# RPiDuino_revA.net
KiCad netlist of a schematic drawn in EAGLE
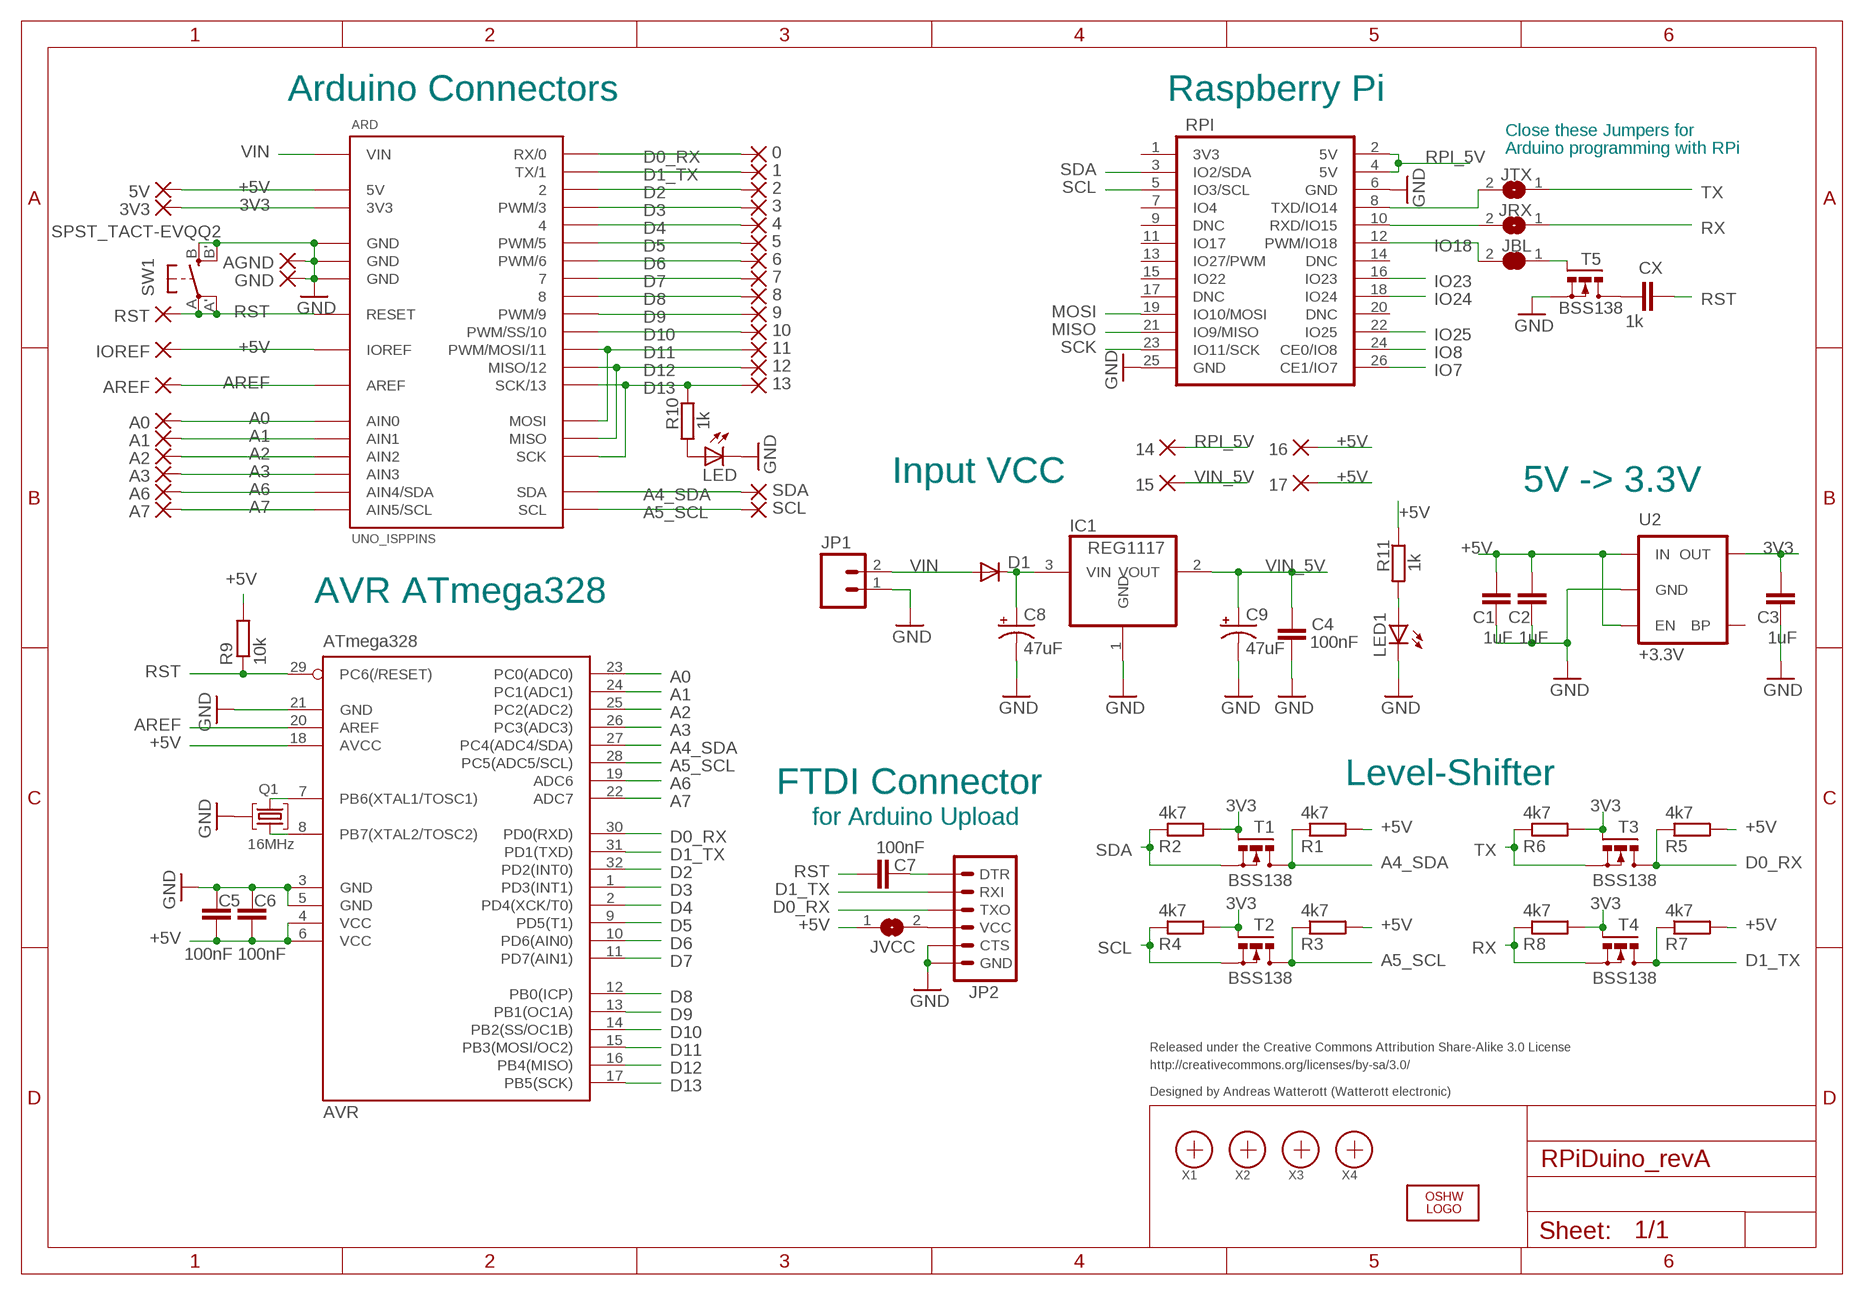
[diagram p0: schematic, sheet 1]

(export (version "E")
  (design (tool "Eeschema 10.0.6"))
  (components
    (comp (ref "0")
      (value "WIREPAD1,6/0,9")
      (footprint "eagle-import:1,6_0,9")
      (libsource (lib "eagle-import") (part "WIREPAD1,6/0,9"))
    )
    (comp (ref "1")
      (value "WIREPAD1,6/0,9")
      (footprint "eagle-import:1,6_0,9")
      (libsource (lib "eagle-import") (part "WIREPAD1,6/0,9"))
    )
    (comp (ref "2")
      (value "WIREPAD1,6/0,9")
      (footprint "eagle-import:1,6_0,9")
      (libsource (lib "eagle-import") (part "WIREPAD1,6/0,9"))
    )
    (comp (ref "3")
      (value "WIREPAD1,6/0,9")
      (footprint "eagle-import:1,6_0,9")
      (libsource (lib "eagle-import") (part "WIREPAD1,6/0,9"))
    )
    (comp (ref "3V3")
      (value "WIREPAD1,6/0,9")
      (footprint "eagle-import:1,6_0,9")
      (libsource (lib "eagle-import") (part "WIREPAD1,6/0,9"))
    )
    (comp (ref "4")
      (value "WIREPAD1,6/0,9")
      (footprint "eagle-import:1,6_0,9")
      (libsource (lib "eagle-import") (part "WIREPAD1,6/0,9"))
    )
    (comp (ref "5")
      (value "WIREPAD1,6/0,9")
      (footprint "eagle-import:1,6_0,9")
      (libsource (lib "eagle-import") (part "WIREPAD1,6/0,9"))
    )
    (comp (ref "5V")
      (value "WIREPAD1,6/0,9")
      (footprint "eagle-import:1,6_0,9")
      (libsource (lib "eagle-import") (part "WIREPAD1,6/0,9"))
    )
    (comp (ref "6")
      (value "WIREPAD1,6/0,9")
      (footprint "eagle-import:1,6_0,9")
      (libsource (lib "eagle-import") (part "WIREPAD1,6/0,9"))
    )
    (comp (ref "7")
      (value "WIREPAD1,6/0,9")
      (footprint "eagle-import:1,6_0,9")
      (libsource (lib "eagle-import") (part "WIREPAD1,6/0,9"))
    )
    (comp (ref "8")
      (value "WIREPAD1,6/0,9")
      (footprint "eagle-import:1,6_0,9")
      (libsource (lib "eagle-import") (part "WIREPAD1,6/0,9"))
    )
    (comp (ref "9")
      (value "WIREPAD1,6/0,9")
      (footprint "eagle-import:1,6_0,9")
      (libsource (lib "eagle-import") (part "WIREPAD1,6/0,9"))
    )
    (comp (ref "10")
      (value "WIREPAD1,6/0,9")
      (footprint "eagle-import:1,6_0,9")
      (libsource (lib "eagle-import") (part "WIREPAD1,6/0,9"))
    )
    (comp (ref "11")
      (value "WIREPAD1,6/0,9")
      (footprint "eagle-import:1,6_0,9")
      (libsource (lib "eagle-import") (part "WIREPAD1,6/0,9"))
    )
    (comp (ref "12")
      (value "WIREPAD1,6/0,9")
      (footprint "eagle-import:1,6_0,9")
      (libsource (lib "eagle-import") (part "WIREPAD1,6/0,9"))
    )
    (comp (ref "13")
      (value "WIREPAD1,6/0,9")
      (footprint "eagle-import:1,6_0,9")
      (libsource (lib "eagle-import") (part "WIREPAD1,6/0,9"))
    )
    (comp (ref "14")
      (value "WIREPAD1,6/0,9")
      (footprint "eagle-import:1,6_0,9")
      (libsource (lib "eagle-import") (part "WIREPAD1,6/0,9"))
    )
    (comp (ref "15")
      (value "WIREPAD1,6/0,9")
      (footprint "eagle-import:1,6_0,9")
      (libsource (lib "eagle-import") (part "WIREPAD1,6/0,9"))
    )
    (comp (ref "16")
      (value "WIREPAD1,6/0,9")
      (footprint "eagle-import:1,6_0,9")
      (libsource (lib "eagle-import") (part "WIREPAD1,6/0,9"))
    )
    (comp (ref "17")
      (value "WIREPAD1,6/0,9")
      (footprint "eagle-import:1,6_0,9")
      (libsource (lib "eagle-import") (part "WIREPAD1,6/0,9"))
    )
    (comp (ref "A0")
      (value "WIREPAD1,6/0,9")
      (footprint "eagle-import:1,6_0,9")
      (libsource (lib "eagle-import") (part "WIREPAD1,6/0,9"))
    )
    (comp (ref "A1")
      (value "WIREPAD1,6/0,9")
      (footprint "eagle-import:1,6_0,9")
      (libsource (lib "eagle-import") (part "WIREPAD1,6/0,9"))
    )
    (comp (ref "A2")
      (value "WIREPAD1,6/0,9")
      (footprint "eagle-import:1,6_0,9")
      (libsource (lib "eagle-import") (part "WIREPAD1,6/0,9"))
    )
    (comp (ref "A3")
      (value "WIREPAD1,6/0,9")
      (footprint "eagle-import:1,6_0,9")
      (libsource (lib "eagle-import") (part "WIREPAD1,6/0,9"))
    )
    (comp (ref "A6")
      (value "WIREPAD1,6/0,9")
      (footprint "eagle-import:1,6_0,9")
      (libsource (lib "eagle-import") (part "WIREPAD1,6/0,9"))
    )
    (comp (ref "A7")
      (value "WIREPAD1,6/0,9")
      (footprint "eagle-import:1,6_0,9")
      (libsource (lib "eagle-import") (part "WIREPAD1,6/0,9"))
    )
    (comp (ref "AGND")
      (value "WIREPAD1,6/0,9")
      (footprint "eagle-import:1,6_0,9")
      (libsource (lib "eagle-import") (part "WIREPAD1,6/0,9"))
    )
    (comp (ref "ARD")
      (value "UNO_ISPPINS")
      (footprint "eagle-import:UNO_ISP3")
      (libsource (lib "eagle-import") (part "UNO_ISPPINS"))
    )
    (comp (ref "AREF")
      (value "WIREPAD1,6/0,9")
      (footprint "eagle-import:1,6_0,9")
      (libsource (lib "eagle-import") (part "WIREPAD1,6/0,9"))
    )
    (comp (ref "AVR")
      (value "ATmega328")
      (footprint "eagle-import:TQFP32-08")
      (fields (field (name "MPN") "ATMEGA8-16AU"))
      (libsource (lib "eagle-import") (part "MEGA8-AI"))
    )
    (comp (ref "C1")
      (value "1uF")
      (footprint "eagle-import:C0603")
      (libsource (lib "eagle-import") (part "C-EUC0603"))
    )
    (comp (ref "C2")
      (value "1uF")
      (footprint "eagle-import:C0603")
      (libsource (lib "eagle-import") (part "C-EUC0603"))
    )
    (comp (ref "C3")
      (value "1uF")
      (footprint "eagle-import:C0603")
      (libsource (lib "eagle-import") (part "C-EUC0603"))
    )
    (comp (ref "C4")
      (value "100nF")
      (footprint "eagle-import:C0603")
      (libsource (lib "eagle-import") (part "C-EUC0603"))
    )
    (comp (ref "C5")
      (value "100nF")
      (footprint "eagle-import:C0603")
      (libsource (lib "eagle-import") (part "C-EUC0603"))
    )
    (comp (ref "C6")
      (value "100nF")
      (footprint "eagle-import:C0603")
      (libsource (lib "eagle-import") (part "C-EUC0603"))
    )
    (comp (ref "C7")
      (value "100nF")
      (footprint "eagle-import:C0603")
      (libsource (lib "eagle-import") (part "C-EUC0603"))
    )
    (comp (ref "C8")
      (value "47uF")
      (footprint "eagle-import:PANASONIC_D")
      (libsource (lib "eagle-import") (part "CAP_POLD"))
    )
    (comp (ref "C9")
      (value "47uF")
      (footprint "eagle-import:PANASONIC_D")
      (libsource (lib "eagle-import") (part "CAP_POLD"))
    )
    (comp (ref "CX")
      (value "1k")
      (footprint "eagle-import:C0603")
      (libsource (lib "eagle-import") (part "C-EUC0603"))
    )
    (comp (ref "D1")
      (value "DIODESMA")
      (footprint "eagle-import:SMA-DIODE")
      (libsource (lib "eagle-import") (part "DIODESMA"))
    )
    (comp (ref "GND")
      (value "WIREPAD1,6/0,9")
      (footprint "eagle-import:1,6_0,9")
      (libsource (lib "eagle-import") (part "WIREPAD1,6/0,9"))
    )
    (comp (ref "IC1")
      (value "REG1117")
      (footprint "eagle-import:SOT223")
      (libsource (lib "eagle-import") (part "REG1117"))
    )
    (comp (ref "IOREF")
      (value "WIREPAD1,6/0,9")
      (footprint "eagle-import:1,6_0,9")
      (libsource (lib "eagle-import") (part "WIREPAD1,6/0,9"))
    )
    (comp (ref "JBL") (value "SJ") (footprint "eagle-import:SJ") (libsource (lib "eagle-import") (part "SJ")))
    (comp (ref "JP1")
      (value "M02PTH")
      (footprint "eagle-import:1X02")
      (libsource (lib "eagle-import") (part "M02PTH"))
    )
    (comp (ref "JP2")
      (value "ARDUINO_SERIAL_PROGRAMPTH")
      (footprint "eagle-import:1X06")
      (libsource (lib "eagle-import") (part "ARDUINO_SERIAL_PROGRAMPTH"))
    )
    (comp (ref "JRX") (value "SJ") (footprint "eagle-import:SJ") (libsource (lib "eagle-import") (part "SJ")))
    (comp (ref "JTX") (value "SJ") (footprint "eagle-import:SJ") (libsource (lib "eagle-import") (part "SJ")))
    (comp (ref "JVCC")
      (value "SJ")
      (footprint "eagle-import:SJ")
      (libsource (lib "eagle-import") (part "SJ"))
    )
    (comp (ref "LED")
      (value "LEDCHIPLED_0603")
      (footprint "eagle-import:CHIPLED_0603")
      (libsource (lib "eagle-import") (part "LEDCHIPLED_0603"))
    )
    (comp (ref "LED1")
      (value "LEDCHIPLED_0603")
      (footprint "eagle-import:CHIPLED_0603")
      (libsource (lib "eagle-import") (part "LEDCHIPLED_0603"))
    )
    (comp (ref "LOGO1")
      (value "OSHW_LOGO_6MILX0150-NT")
      (footprint "eagle-import:OSHW_6X150_NOTEXT")
      (libsource (lib "eagle-import") (part "OSHW_LOGO_6MILX0150-NT"))
    )
    (comp (ref "Q1")
      (value "16MHz")
      (footprint "eagle-import:SMD_OSC_35X15")
      (libsource (lib "eagle-import") (part "SMD_OSC2"))
    )
    (comp (ref "R1")
      (value "4k7")
      (footprint "eagle-import:R0603")
      (libsource (lib "eagle-import") (part "R-EU_R0603"))
    )
    (comp (ref "R2")
      (value "4k7")
      (footprint "eagle-import:R0603")
      (libsource (lib "eagle-import") (part "R-EU_R0603"))
    )
    (comp (ref "R3")
      (value "4k7")
      (footprint "eagle-import:R0603")
      (libsource (lib "eagle-import") (part "R-EU_R0603"))
    )
    (comp (ref "R4")
      (value "4k7")
      (footprint "eagle-import:R0603")
      (libsource (lib "eagle-import") (part "R-EU_R0603"))
    )
    (comp (ref "R5")
      (value "4k7")
      (footprint "eagle-import:R0603")
      (libsource (lib "eagle-import") (part "R-EU_R0603"))
    )
    (comp (ref "R6")
      (value "4k7")
      (footprint "eagle-import:R0603")
      (libsource (lib "eagle-import") (part "R-EU_R0603"))
    )
    (comp (ref "R7")
      (value "4k7")
      (footprint "eagle-import:R0603")
      (libsource (lib "eagle-import") (part "R-EU_R0603"))
    )
    (comp (ref "R8")
      (value "4k7")
      (footprint "eagle-import:R0603")
      (libsource (lib "eagle-import") (part "R-EU_R0603"))
    )
    (comp (ref "R9")
      (value "10k")
      (footprint "eagle-import:R0603")
      (libsource (lib "eagle-import") (part "R-EU_R0603"))
    )
    (comp (ref "R10")
      (value "1k")
      (footprint "eagle-import:R0603")
      (libsource (lib "eagle-import") (part "R-EU_R0603"))
    )
    (comp (ref "R11")
      (value "1k")
      (footprint "eagle-import:R0603")
      (libsource (lib "eagle-import") (part "R-EU_R0603"))
    )
    (comp (ref "RPI")
      (value "RPI")
      (footprint "eagle-import:RPI")
      (libsource (lib "eagle-import") (part "RPI"))
    )
    (comp (ref "RST")
      (value "WIREPAD1,6/0,9")
      (footprint "eagle-import:1,6_0,9")
      (libsource (lib "eagle-import") (part "WIREPAD1,6/0,9"))
    )
    (comp (ref "SCL")
      (value "WIREPAD1,6/0,9")
      (footprint "eagle-import:1,6_0,9")
      (libsource (lib "eagle-import") (part "WIREPAD1,6/0,9"))
    )
    (comp (ref "SDA")
      (value "WIREPAD1,6/0,9")
      (footprint "eagle-import:1,6_0,9")
      (libsource (lib "eagle-import") (part "WIREPAD1,6/0,9"))
    )
    (comp (ref "SW1")
      (value "SPST_TACT-EVQQ2")
      (footprint "eagle-import:EVQ-Q2")
      (libsource (lib "eagle-import") (part "SPST_TACT-EVQQ2"))
    )
    (comp (ref "T1")
      (value "BSS138")
      (footprint "eagle-import:MICRO3")
      (libsource (lib "eagle-import") (part "IRLML2502"))
    )
    (comp (ref "T2")
      (value "BSS138")
      (footprint "eagle-import:MICRO3")
      (libsource (lib "eagle-import") (part "IRLML2502"))
    )
    (comp (ref "T3")
      (value "BSS138")
      (footprint "eagle-import:MICRO3")
      (libsource (lib "eagle-import") (part "IRLML2502"))
    )
    (comp (ref "T4")
      (value "BSS138")
      (footprint "eagle-import:MICRO3")
      (libsource (lib "eagle-import") (part "IRLML2502"))
    )
    (comp (ref "T5")
      (value "BSS138")
      (footprint "eagle-import:MICRO3")
      (libsource (lib "eagle-import") (part "IRLML2502"))
    )
    (comp (ref "U2")
      (value "MIC52053.3V")
      (footprint "eagle-import:SOT23-5")
      (libsource (lib "eagle-import") (part "MIC52053.3V"))
    )
    (comp (ref "X1")
      (value "PASSER")
      (footprint "eagle-import:PASSER")
      (libsource (lib "eagle-import") (part "PASSER"))
    )
    (comp (ref "X2")
      (value "PASSER")
      (footprint "eagle-import:PASSER")
      (libsource (lib "eagle-import") (part "PASSER"))
    )
    (comp (ref "X3")
      (value "PASSER")
      (footprint "eagle-import:PASSER")
      (libsource (lib "eagle-import") (part "PASSER"))
    )
    (comp (ref "X4")
      (value "PASSER")
      (footprint "eagle-import:PASSER")
      (libsource (lib "eagle-import") (part "PASSER"))
    )
  )
  (nets
    (net (code "1") (name "/+5V") (class "Default")
      (node (ref "16") (pin "1") (pinfunction "P_1") (pintype "passive"))
      (node (ref "17") (pin "1") (pinfunction "P_1") (pintype "passive"))
      (node (ref "5V") (pin "1") (pinfunction "P_1") (pintype "passive"))
      (node (ref "ARD") (pin "5V") (pinfunction "5V_5V") (pintype "power_in"))
      (node (ref "ARD") (pin "IOREF") (pinfunction "IOREF_IOREF") (pintype "power_in"))
      (node (ref "AVR") (pin "18") (pinfunction "AVCC_18") (pintype "power_in"))
      (node (ref "AVR") (pin "4") (pinfunction "VCC_4") (pintype "power_in"))
      (node (ref "AVR") (pin "6") (pinfunction "VCC_6") (pintype "power_in"))
      (node (ref "C1") (pin "1") (pinfunction "1_1") (pintype "passive"))
      (node (ref "C2") (pin "1") (pinfunction "1_1") (pintype "passive"))
      (node (ref "C5") (pin "1") (pinfunction "1_1") (pintype "passive"))
      (node (ref "C6") (pin "1") (pinfunction "1_1") (pintype "passive"))
      (node (ref "IOREF") (pin "1") (pinfunction "P_1") (pintype "passive"))
      (node (ref "JVCC") (pin "1") (pinfunction "1_1") (pintype "passive"))
      (node (ref "R1") (pin "2") (pinfunction "2_2") (pintype "passive"))
      (node (ref "R11") (pin "1") (pinfunction "1_1") (pintype "passive"))
      (node (ref "R3") (pin "2") (pinfunction "2_2") (pintype "passive"))
      (node (ref "R5") (pin "2") (pinfunction "2_2") (pintype "passive"))
      (node (ref "R7") (pin "2") (pinfunction "2_2") (pintype "passive"))
      (node (ref "R9") (pin "2") (pinfunction "2_2") (pintype "passive"))
      (node (ref "U2") (pin "1") (pinfunction "IN_1") (pintype "input"))
      (node (ref "U2") (pin "3") (pinfunction "EN_3") (pintype "input"))
    )
    (net (code "2") (name "/3V3") (class "Default")
      (node (ref "3V3") (pin "1") (pinfunction "P_1") (pintype "passive"))
      (node (ref "ARD") (pin "3V3") (pinfunction "3V3_3V3") (pintype "power_in"))
      (node (ref "C3") (pin "1") (pinfunction "1_1") (pintype "passive"))
      (node (ref "R2") (pin "2") (pinfunction "2_2") (pintype "passive"))
      (node (ref "R4") (pin "2") (pinfunction "2_2") (pintype "passive"))
      (node (ref "R6") (pin "2") (pinfunction "2_2") (pintype "passive"))
      (node (ref "R8") (pin "2") (pinfunction "2_2") (pintype "passive"))
      (node (ref "T1") (pin "1") (pinfunction "G_1") (pintype "passive"))
      (node (ref "T2") (pin "1") (pinfunction "G_1") (pintype "passive"))
      (node (ref "T3") (pin "1") (pinfunction "G_1") (pintype "passive"))
      (node (ref "T4") (pin "1") (pinfunction "G_1") (pintype "passive"))
      (node (ref "U2") (pin "5") (pinfunction "OUT_5") (pintype "passive"))
    )
    (net (code "3") (name "/A0") (class "Default")
      (node (ref "A0") (pin "1") (pinfunction "P_1") (pintype "passive"))
      (node (ref "ARD") (pin "AIN0") (pinfunction "AIN0_AIN0") (pintype "bidirectional"))
      (node (ref "AVR") (pin "23") (pinfunction "PC0(ADC0)_23") (pintype "bidirectional"))
    )
    (net (code "4") (name "/A1") (class "Default")
      (node (ref "A1") (pin "1") (pinfunction "P_1") (pintype "passive"))
      (node (ref "ARD") (pin "AIN1") (pinfunction "AIN1_AIN1") (pintype "bidirectional"))
      (node (ref "AVR") (pin "24") (pinfunction "PC1(ADC1)_24") (pintype "bidirectional"))
    )
    (net (code "5") (name "/A2") (class "Default")
      (node (ref "A2") (pin "1") (pinfunction "P_1") (pintype "passive"))
      (node (ref "ARD") (pin "AIN2") (pinfunction "AIN2_AIN2") (pintype "bidirectional"))
      (node (ref "AVR") (pin "25") (pinfunction "PC2(ADC2)_25") (pintype "bidirectional"))
    )
    (net (code "6") (name "/A3") (class "Default")
      (node (ref "A3") (pin "1") (pinfunction "P_1") (pintype "passive"))
      (node (ref "ARD") (pin "AIN3") (pinfunction "AIN3_AIN3") (pintype "bidirectional"))
      (node (ref "AVR") (pin "26") (pinfunction "PC3(ADC3)_26") (pintype "bidirectional"))
    )
    (net (code "7") (name "/A4_SDA") (class "Default")
      (node (ref "ARD") (pin "SDA") (pinfunction "SDA_SDA") (pintype "bidirectional"))
      (node (ref "AVR") (pin "27") (pinfunction "PC4(ADC4/SDA)_27") (pintype "bidirectional"))
      (node (ref "R1") (pin "1") (pinfunction "1_1") (pintype "passive"))
      (node (ref "SDA") (pin "1") (pinfunction "P_1") (pintype "passive"))
      (node (ref "T1") (pin "3") (pinfunction "D_3") (pintype "passive"))
    )
    (net (code "8") (name "/A5_SCL") (class "Default")
      (node (ref "ARD") (pin "SCL") (pinfunction "SCL_SCL") (pintype "bidirectional"))
      (node (ref "AVR") (pin "28") (pinfunction "PC5(ADC5/SCL)_28") (pintype "bidirectional"))
      (node (ref "R3") (pin "1") (pinfunction "1_1") (pintype "passive"))
      (node (ref "SCL") (pin "1") (pinfunction "P_1") (pintype "passive"))
      (node (ref "T2") (pin "3") (pinfunction "D_3") (pintype "passive"))
    )
    (net (code "9") (name "/A6") (class "Default")
      (node (ref "A6") (pin "1") (pinfunction "P_1") (pintype "passive"))
      (node (ref "ARD") (pin "AIN4") (pinfunction "AIN4/SDA_AIN4") (pintype "bidirectional"))
      (node (ref "AVR") (pin "19") (pinfunction "ADC6_19") (pintype "bidirectional"))
    )
    (net (code "10") (name "/A7") (class "Default")
      (node (ref "A7") (pin "1") (pinfunction "P_1") (pintype "passive"))
      (node (ref "ARD") (pin "AIN5") (pinfunction "AIN5/SCL_AIN5") (pintype "bidirectional"))
      (node (ref "AVR") (pin "22") (pinfunction "ADC7_22") (pintype "bidirectional"))
    )
    (net (code "11") (name "/AREF") (class "Default")
      (node (ref "ARD") (pin "AREF") (pinfunction "AREF_AREF") (pintype "power_in"))
      (node (ref "AREF") (pin "1") (pinfunction "P_1") (pintype "passive"))
      (node (ref "AVR") (pin "20") (pinfunction "AREF_20") (pintype "passive"))
    )
    (net (code "12") (name "/D0_RX") (class "Default")
      (node (ref "0") (pin "1") (pinfunction "P_1") (pintype "passive"))
      (node (ref "ARD") (pin "0") (pinfunction "RX/0_0") (pintype "bidirectional"))
      (node (ref "AVR") (pin "30") (pinfunction "PD0(RXD)_30") (pintype "bidirectional"))
      (node (ref "JP2") (pin "3") (pinfunction "TXO_3") (pintype "passive"))
      (node (ref "R5") (pin "1") (pinfunction "1_1") (pintype "passive"))
      (node (ref "T3") (pin "3") (pinfunction "D_3") (pintype "passive"))
    )
    (net (code "13") (name "/D1_TX") (class "Default")
      (node (ref "1") (pin "1") (pinfunction "P_1") (pintype "passive"))
      (node (ref "ARD") (pin "1") (pinfunction "TX/1_1") (pintype "bidirectional"))
      (node (ref "AVR") (pin "31") (pinfunction "PD1(TXD)_31") (pintype "bidirectional"))
      (node (ref "JP2") (pin "2") (pinfunction "RXI_2") (pintype "passive"))
      (node (ref "R7") (pin "1") (pinfunction "1_1") (pintype "passive"))
      (node (ref "T4") (pin "3") (pinfunction "D_3") (pintype "passive"))
    )
    (net (code "14") (name "/D2") (class "Default")
      (node (ref "2") (pin "1") (pinfunction "P_1") (pintype "passive"))
      (node (ref "ARD") (pin "2") (pinfunction "2_2") (pintype "bidirectional"))
      (node (ref "AVR") (pin "32") (pinfunction "PD2(INT0)_32") (pintype "bidirectional"))
    )
    (net (code "15") (name "/D3") (class "Default")
      (node (ref "3") (pin "1") (pinfunction "P_1") (pintype "passive"))
      (node (ref "ARD") (pin "3") (pinfunction "PWM/3_3") (pintype "bidirectional"))
      (node (ref "AVR") (pin "1") (pinfunction "PD3(INT1)_1") (pintype "bidirectional"))
    )
    (net (code "16") (name "/D4") (class "Default")
      (node (ref "4") (pin "1") (pinfunction "P_1") (pintype "passive"))
      (node (ref "ARD") (pin "4") (pinfunction "4_4") (pintype "bidirectional"))
      (node (ref "AVR") (pin "2") (pinfunction "PD4(XCK/T0)_2") (pintype "bidirectional"))
    )
    (net (code "17") (name "/D5") (class "Default")
      (node (ref "5") (pin "1") (pinfunction "P_1") (pintype "passive"))
      (node (ref "ARD") (pin "5") (pinfunction "PWM/5_5") (pintype "bidirectional"))
      (node (ref "AVR") (pin "9") (pinfunction "PD5(T1)_9") (pintype "bidirectional"))
    )
    (net (code "18") (name "/D6") (class "Default")
      (node (ref "6") (pin "1") (pinfunction "P_1") (pintype "passive"))
      (node (ref "ARD") (pin "6") (pinfunction "PWM/6_6") (pintype "bidirectional"))
      (node (ref "AVR") (pin "10") (pinfunction "PD6(AIN0)_10") (pintype "bidirectional"))
    )
    (net (code "19") (name "/D7") (class "Default")
      (node (ref "7") (pin "1") (pinfunction "P_1") (pintype "passive"))
      (node (ref "ARD") (pin "7") (pinfunction "7_7") (pintype "bidirectional"))
      (node (ref "AVR") (pin "11") (pinfunction "PD7(AIN1)_11") (pintype "bidirectional"))
    )
    (net (code "20") (name "/D8") (class "Default")
      (node (ref "8") (pin "1") (pinfunction "P_1") (pintype "passive"))
      (node (ref "ARD") (pin "8") (pinfunction "8_8") (pintype "bidirectional"))
      (node (ref "AVR") (pin "12") (pinfunction "PB0(ICP)_12") (pintype "bidirectional"))
    )
    (net (code "21") (name "/D9") (class "Default")
      (node (ref "9") (pin "1") (pinfunction "P_1") (pintype "passive"))
      (node (ref "ARD") (pin "9") (pinfunction "PWM/9_9") (pintype "bidirectional"))
      (node (ref "AVR") (pin "13") (pinfunction "PB1(OC1A)_13") (pintype "bidirectional"))
    )
    (net (code "22") (name "/D10") (class "Default")
      (node (ref "10") (pin "1") (pinfunction "P_1") (pintype "passive"))
      (node (ref "ARD") (pin "10") (pinfunction "PWM/SS/10_10") (pintype "bidirectional"))
      (node (ref "AVR") (pin "14") (pinfunction "PB2(SS/OC1B)_14") (pintype "bidirectional"))
    )
    (net (code "23") (name "/D11") (class "Default")
      (node (ref "11") (pin "1") (pinfunction "P_1") (pintype "passive"))
      (node (ref "ARD") (pin "11") (pinfunction "PWM/MOSI/11_11") (pintype "bidirectional"))
      (node (ref "ARD") (pin "MOSI") (pinfunction "MOSI_MOSI") (pintype "bidirectional"))
      (node (ref "AVR") (pin "15") (pinfunction "PB3(MOSI/OC2)_15") (pintype "bidirectional"))
    )
    (net (code "24") (name "/D12") (class "Default")
      (node (ref "12") (pin "1") (pinfunction "P_1") (pintype "passive"))
      (node (ref "ARD") (pin "12") (pinfunction "MISO/12_12") (pintype "bidirectional"))
      (node (ref "ARD") (pin "MISO") (pinfunction "MISO_MISO") (pintype "bidirectional"))
      (node (ref "AVR") (pin "16") (pinfunction "PB4(MISO)_16") (pintype "bidirectional"))
    )
    (net (code "25") (name "/D13") (class "Default")
      (node (ref "13") (pin "1") (pinfunction "P_1") (pintype "passive"))
      (node (ref "ARD") (pin "13") (pinfunction "SCK/13_13") (pintype "bidirectional"))
      (node (ref "ARD") (pin "SCK") (pinfunction "SCK_SCK") (pintype "bidirectional"))
      (node (ref "AVR") (pin "17") (pinfunction "PB5(SCK)_17") (pintype "bidirectional"))
      (node (ref "R10") (pin "1") (pinfunction "1_1") (pintype "passive"))
    )
    (net (code "26") (name "/IO7") (class "Default")
      (node (ref "RPI") (pin "26") (pinfunction "CE1/IO7_26") (pintype "passive"))
    )
    (net (code "27") (name "/IO8") (class "Default")
      (node (ref "RPI") (pin "24") (pinfunction "CE0/IO8_24") (pintype "passive"))
    )
    (net (code "28") (name "/IO18") (class "Default")
      (node (ref "JBL") (pin "2") (pinfunction "2_2") (pintype "passive"))
      (node (ref "RPI") (pin "12") (pinfunction "PWM/IO18_12") (pintype "passive"))
    )
    (net (code "29") (name "/IO23") (class "Default")
      (node (ref "RPI") (pin "16") (pinfunction "IO23_16") (pintype "passive"))
    )
    (net (code "30") (name "/IO24") (class "Default")
      (node (ref "RPI") (pin "18") (pinfunction "IO24_18") (pintype "passive"))
    )
    (net (code "31") (name "/IO25") (class "Default")
      (node (ref "RPI") (pin "22") (pinfunction "IO25_22") (pintype "passive"))
    )
    (net (code "32") (name "/MISO") (class "Default")
      (node (ref "RPI") (pin "21") (pinfunction "IO9/MISO_21") (pintype "passive"))
    )
    (net (code "33") (name "/MOSI") (class "Default")
      (node (ref "RPI") (pin "19") (pinfunction "IO10/MOSI_19") (pintype "passive"))
    )
    (net (code "34") (name "/RPI_5V") (class "Default")
      (node (ref "14") (pin "1") (pinfunction "P_1") (pintype "passive"))
      (node (ref "RPI") (pin "2") (pinfunction "5V_2") (pintype "passive"))
      (node (ref "RPI") (pin "4") (pinfunction "5V_4") (pintype "passive"))
    )
    (net (code "35") (name "/RST") (class "Default")
      (node (ref "ARD") (pin "RST") (pinfunction "RESET_RST") (pintype "bidirectional"))
      (node (ref "AVR") (pin "29") (pinfunction "PC6(/RESET)_29") (pintype "bidirectional"))
      (node (ref "C7") (pin "2") (pinfunction "2_2") (pintype "passive"))
      (node (ref "CX") (pin "2") (pinfunction "2_2") (pintype "passive"))
      (node (ref "R9") (pin "1") (pinfunction "1_1") (pintype "passive"))
      (node (ref "RST") (pin "1") (pinfunction "P_1") (pintype "passive"))
      (node (ref "SW1") (pin "A") (pinfunction "P_A") (pintype "passive"))
      (node (ref "SW1") (pin "A'") (pinfunction "P1_A'") (pintype "passive"))
    )
    (net (code "36") (name "/RX") (class "Default")
      (node (ref "JRX") (pin "1") (pinfunction "1_1") (pintype "passive"))
      (node (ref "R8") (pin "1") (pinfunction "1_1") (pintype "passive"))
      (node (ref "T4") (pin "2") (pinfunction "S_2") (pintype "passive"))
    )
    (net (code "37") (name "/SCK") (class "Default")
      (node (ref "RPI") (pin "23") (pinfunction "IO11/SCK_23") (pintype "passive"))
    )
    (net (code "38") (name "/SCL") (class "Default")
      (node (ref "R4") (pin "1") (pinfunction "1_1") (pintype "passive"))
      (node (ref "RPI") (pin "5") (pinfunction "IO3/SCL_5") (pintype "passive"))
      (node (ref "T2") (pin "2") (pinfunction "S_2") (pintype "passive"))
    )
    (net (code "39") (name "/SDA") (class "Default")
      (node (ref "R2") (pin "1") (pinfunction "1_1") (pintype "passive"))
      (node (ref "RPI") (pin "3") (pinfunction "IO2/SDA_3") (pintype "passive"))
      (node (ref "T1") (pin "2") (pinfunction "S_2") (pintype "passive"))
    )
    (net (code "40") (name "/TX") (class "Default")
      (node (ref "JTX") (pin "1") (pinfunction "1_1") (pintype "passive"))
      (node (ref "R6") (pin "1") (pinfunction "1_1") (pintype "passive"))
      (node (ref "T3") (pin "2") (pinfunction "S_2") (pintype "passive"))
    )
    (net (code "41") (name "/VIN") (class "Default")
      (node (ref "ARD") (pin "VIN") (pinfunction "VIN_VIN") (pintype "power_in"))
      (node (ref "D1") (pin "A") (pinfunction "A_A") (pintype "passive"))
      (node (ref "JP1") (pin "2") (pinfunction "2_2") (pintype "passive"))
    )
    (net (code "42") (name "/VIN_5V") (class "Default")
      (node (ref "15") (pin "1") (pinfunction "P_1") (pintype "passive"))
      (node (ref "C4") (pin "1") (pinfunction "1_1") (pintype "passive"))
      (node (ref "C9") (pin "+") (pinfunction "+_+") (pintype "passive"))
      (node (ref "IC1") (pin "2") (pinfunction "VOUT_2") (pintype "output"))
    )
    (net (code "43") (name "GND") (class "Default")
      (node (ref "AGND") (pin "1") (pinfunction "P_1") (pintype "passive"))
      (node (ref "ARD") (pin "GND@1") (pinfunction "GND_GND@1") (pintype "power_in"))
      (node (ref "ARD") (pin "GND@2") (pinfunction "GND_GND@2") (pintype "power_in"))
      (node (ref "ARD") (pin "GND@3") (pinfunction "GND_GND@3") (pintype "power_in"))
      (node (ref "AVR") (pin "21") (pinfunction "GND_21") (pintype "power_in"))
      (node (ref "AVR") (pin "3") (pinfunction "GND_3") (pintype "power_in"))
      (node (ref "AVR") (pin "5") (pinfunction "GND_5") (pintype "power_in"))
      (node (ref "C1") (pin "2") (pinfunction "2_2") (pintype "passive"))
      (node (ref "C2") (pin "2") (pinfunction "2_2") (pintype "passive"))
      (node (ref "C3") (pin "2") (pinfunction "2_2") (pintype "passive"))
      (node (ref "C4") (pin "2") (pinfunction "2_2") (pintype "passive"))
      (node (ref "C5") (pin "2") (pinfunction "2_2") (pintype "passive"))
      (node (ref "C6") (pin "2") (pinfunction "2_2") (pintype "passive"))
      (node (ref "C8") (pin "-") (pinfunction "-_-") (pintype "passive"))
      (node (ref "C9") (pin "-") (pinfunction "-_-") (pintype "passive"))
      (node (ref "GND") (pin "1") (pinfunction "P_1") (pintype "passive"))
      (node (ref "IC1") (pin "1") (pinfunction "GND_1") (pintype "power_in"))
      (node (ref "JP1") (pin "1") (pinfunction "1_1") (pintype "passive"))
      (node (ref "JP2") (pin "5") (pinfunction "CTS_5") (pintype "passive"))
      (node (ref "JP2") (pin "6") (pinfunction "GND_6") (pintype "passive"))
      (node (ref "LED") (pin "C") (pinfunction "C_C") (pintype "passive"))
      (node (ref "LED1") (pin "C") (pinfunction "C_C") (pintype "passive"))
      (node (ref "Q1") (pin "GND") (pinfunction "GND_GND") (pintype "passive"))
      (node (ref "RPI") (pin "25") (pinfunction "GND_25") (pintype "passive"))
      (node (ref "RPI") (pin "6") (pinfunction "GND_6") (pintype "passive"))
      (node (ref "SW1") (pin "B") (pinfunction "S_B") (pintype "passive"))
      (node (ref "SW1") (pin "B'") (pinfunction "S1_B'") (pintype "passive"))
      (node (ref "T5") (pin "2") (pinfunction "S_2") (pintype "passive"))
      (node (ref "U2") (pin "2") (pinfunction "GND_2") (pintype "input"))
    )
    (net (code "44") (name "Net-(AVR-PB6(XTAL1{slash}TOSC1))") (class "Default")
      (node (ref "AVR") (pin "7") (pinfunction "PB6(XTAL1/TOSC1)_7") (pintype "bidirectional"))
      (node (ref "Q1") (pin "1") (pinfunction "1_1") (pintype "passive"))
    )
    (net (code "45") (name "Net-(AVR-PB7(XTAL2{slash}TOSC2))") (class "Default")
      (node (ref "AVR") (pin "8") (pinfunction "PB7(XTAL2/TOSC2)_8") (pintype "bidirectional"))
      (node (ref "Q1") (pin "2") (pinfunction "2_2") (pintype "passive"))
    )
    (net (code "46") (name "Net-(IC1-VIN)") (class "Default")
      (node (ref "C8") (pin "+") (pinfunction "+_+") (pintype "passive"))
      (node (ref "D1") (pin "C") (pinfunction "C_C") (pintype "passive"))
      (node (ref "IC1") (pin "3") (pinfunction "VIN_3") (pintype "input"))
    )
    (net (code "47") (name "Net-(JP2-DTR)") (class "Default")
      (node (ref "C7") (pin "1") (pinfunction "1_1") (pintype "passive"))
      (node (ref "JP2") (pin "1") (pinfunction "DTR_1") (pintype "passive"))
    )
    (net (code "48") (name "Net-(JP2-VCC)") (class "Default")
      (node (ref "JP2") (pin "4") (pinfunction "VCC_4") (pintype "passive"))
      (node (ref "JVCC") (pin "2") (pinfunction "2_2") (pintype "passive"))
    )
    (net (code "49") (name "Net-(LED-PadA)") (class "Default")
      (node (ref "LED") (pin "A") (pinfunction "A_A") (pintype "passive"))
      (node (ref "R10") (pin "2") (pinfunction "2_2") (pintype "passive"))
    )
    (net (code "50") (name "Net-(LED1-PadA)") (class "Default")
      (node (ref "LED1") (pin "A") (pinfunction "A_A") (pintype "passive"))
      (node (ref "R11") (pin "2") (pinfunction "2_2") (pintype "passive"))
    )
    (net (code "51") (name "Net-(RPI-RXD{slash}IO15)") (class "Default")
      (node (ref "JRX") (pin "2") (pinfunction "2_2") (pintype "passive"))
      (node (ref "RPI") (pin "10") (pinfunction "RXD/IO15_10") (pintype "passive"))
    )
    (net (code "52") (name "Net-(RPI-TXD{slash}IO14)") (class "Default")
      (node (ref "JTX") (pin "2") (pinfunction "2_2") (pintype "passive"))
      (node (ref "RPI") (pin "8") (pinfunction "TXD/IO14_8") (pintype "passive"))
    )
    (net (code "53") (name "Net-(T5-D)") (class "Default")
      (node (ref "CX") (pin "1") (pinfunction "1_1") (pintype "passive"))
      (node (ref "T5") (pin "3") (pinfunction "D_3") (pintype "passive"))
    )
    (net (code "54") (name "Net-(T5-G)") (class "Default")
      (node (ref "JBL") (pin "1") (pinfunction "1_1") (pintype "passive"))
      (node (ref "T5") (pin "1") (pinfunction "G_1") (pintype "passive"))
    )
    (net (code "55") (name "unconnected-(RPI-3V3-Pad1)") (class "Default")
      (node (ref "RPI") (pin "1") (pinfunction "3V3_1") (pintype "passive"))
    )
    (net (code "56") (name "unconnected-(RPI-DNC-Pad9)") (class "Default")
      (node (ref "RPI") (pin "9") (pinfunction "DNC_9") (pintype "passive"))
    )
    (net (code "57") (name "unconnected-(RPI-DNC-Pad14)") (class "Default")
      (node (ref "RPI") (pin "14") (pinfunction "DNC_14") (pintype "passive"))
    )
    (net (code "58") (name "unconnected-(RPI-DNC-Pad17)") (class "Default")
      (node (ref "RPI") (pin "17") (pinfunction "DNC_17") (pintype "passive"))
    )
    (net (code "59") (name "unconnected-(RPI-DNC-Pad20)") (class "Default")
      (node (ref "RPI") (pin "20") (pinfunction "DNC_20") (pintype "passive"))
    )
    (net (code "60") (name "unconnected-(RPI-IO4-Pad7)") (class "Default")
      (node (ref "RPI") (pin "7") (pinfunction "IO4_7") (pintype "passive"))
    )
    (net (code "61") (name "unconnected-(RPI-IO17-Pad11)") (class "Default")
      (node (ref "RPI") (pin "11") (pinfunction "IO17_11") (pintype "passive"))
    )
    (net (code "62") (name "unconnected-(RPI-IO22-Pad15)") (class "Default")
      (node (ref "RPI") (pin "15") (pinfunction "IO22_15") (pintype "passive"))
    )
    (net (code "63") (name "unconnected-(RPI-IO27{slash}PWM-Pad13)") (class "Default")
      (node (ref "RPI") (pin "13") (pinfunction "IO27/PWM_13") (pintype "passive"))
    )
    (net (code "64") (name "unconnected-(U2-BP-Pad4)") (class "Default")
      (node (ref "U2") (pin "4") (pinfunction "BP_4") (pintype "input"))
    )
  )
)
